# Headlight_Left_Board.net
KiCad netlist of a schematic drawn in Altium Designer
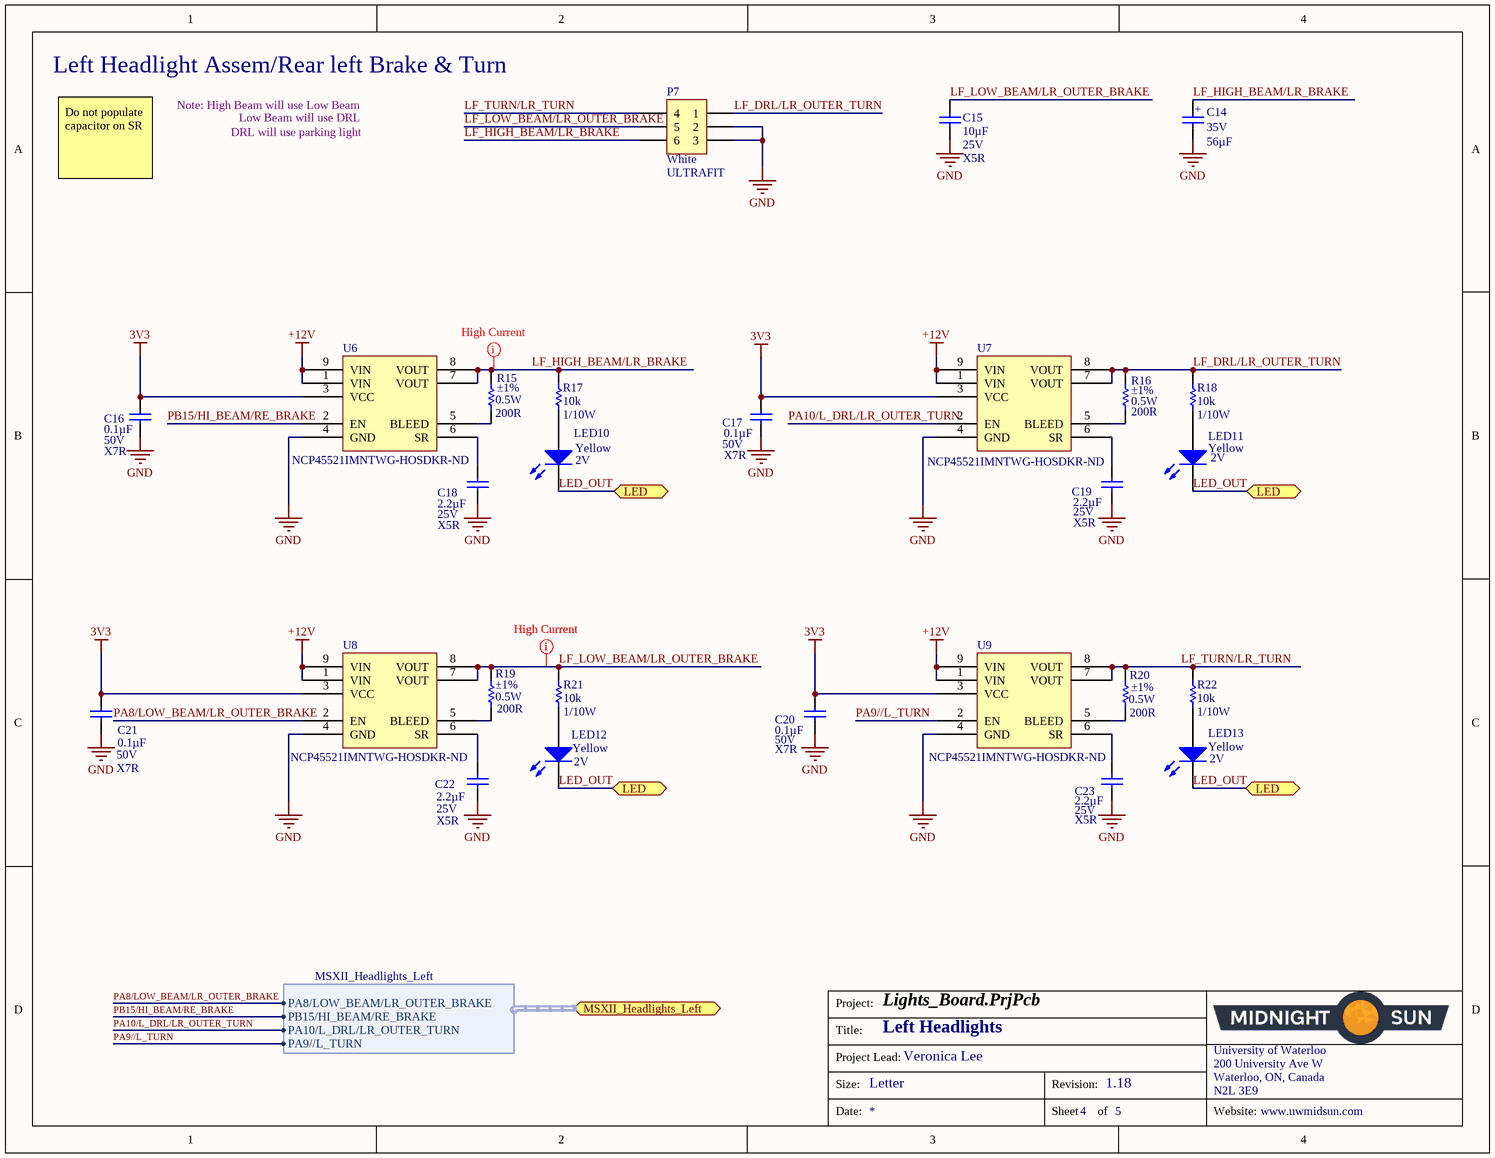
[diagram p0: Headlight_Left_Board.SchDoc]

(export (version "E")
  (design (tool "Eeschema 10.0.6"))
  (components
    (comp (ref "C14")
      (value "CAP ALUM 56UF 20% 35V RADIAL")
      (footprint "CAP ALUM 56UF 20% 35V RADIAL")
      (description "56µF 35V Aluminum Electrolytic Capacitors Radial, Can 1000 Hrs @ 105°C")
      (fields
        (field (name "MANUFACTURER") "Panasonic Electronic Components")
        (field (name "MANUFACTURER PART NUMBER") "EEU-FC1V560H")
        (field (name "VOLTAGE") "35V")
        (field (name "CAPACITANCE") "56µF")
      )
      (libsource (lib "Schematic Diagrams") (part "CAP ALUM 56UF 20% 35V RADIAL"))
    )
    (comp (ref "C15")
      (value "CAP CER 10uF 25V 20% X5R 0603")
      (footprint "CAP, 0603")
      (description "10µF ±20% 25V Ceramic Capacitor X5R 0603 (1608 Metric)")
      (fields
        (field (name "TOLERANCE") "±20%")
        (field (name "CAPACITANCE") "10µF")
        (field (name "VOLTAGE") "25V")
        (field (name "TEMPERATURE COEFFICIENT") "X5R")
      )
      (libsource (lib "Schematic Diagrams") (part "CAP CER 10uF 25V 20% X5R 0603"))
    )
    (comp (ref "C16")
      (value "CAP CER 0.1UF 50V 10% X7R 0603")
      (footprint "CAP, 0603")
      (description "0.10µF ±10% 50V Ceramic Capacitor X7R 0603 (1608 Metric)")
      (fields
        (field (name "TOLERANCE") "±10%")
        (field (name "CAPACITANCE") "0.1µF")
        (field (name "VOLTAGE") "50V")
        (field (name "TEMPERATURE COEFFICIENT") "X7R")
      )
      (libsource (lib "Schematic Diagrams") (part "CAP CER 0.1UF 50V 10% X7R 0603"))
    )
    (comp (ref "C17")
      (value "CAP CER 0.1UF 50V 10% X7R 0603")
      (footprint "CAP, 0603")
      (description "0.10µF ±10% 50V Ceramic Capacitor X7R 0603 (1608 Metric)")
      (fields
        (field (name "TOLERANCE") "±10%")
        (field (name "CAPACITANCE") "0.1µF")
        (field (name "VOLTAGE") "50V")
        (field (name "TEMPERATURE COEFFICIENT") "X7R")
      )
      (libsource (lib "Schematic Diagrams") (part "CAP CER 0.1UF 50V 10% X7R 0603"))
    )
    (comp (ref "C18")
      (value "CAP CER 2.2UF 25V 10% X5R 0603")
      (footprint "CAP, 0603")
      (description "2.2µF ±10% 25V Ceramic Capacitor X5R 0603 (1608 Metric)")
      (fields
        (field (name "TOLERANCE") "±10%")
        (field (name "CAPACITANCE") "2.2µF")
        (field (name "VOLTAGE") "25V")
        (field (name "TEMPERATURE COEFFICIENT") "X5R")
      )
      (libsource (lib "Schematic Diagrams") (part "CAP CER 2.2UF 25V 10% X5R 0603"))
    )
    (comp (ref "C19")
      (value "CAP CER 2.2UF 25V 10% X5R 0603")
      (footprint "CAP, 0603")
      (description "2.2µF ±10% 25V Ceramic Capacitor X5R 0603 (1608 Metric)")
      (fields
        (field (name "TOLERANCE") "±10%")
        (field (name "CAPACITANCE") "2.2µF")
        (field (name "VOLTAGE") "25V")
        (field (name "TEMPERATURE COEFFICIENT") "X5R")
      )
      (libsource (lib "Schematic Diagrams") (part "CAP CER 2.2UF 25V 10% X5R 0603"))
    )
    (comp (ref "C20")
      (value "CAP CER 0.1UF 50V 10% X7R 0603")
      (footprint "CAP, 0603")
      (description "0.10µF ±10% 50V Ceramic Capacitor X7R 0603 (1608 Metric)")
      (fields
        (field (name "TOLERANCE") "±10%")
        (field (name "CAPACITANCE") "0.1µF")
        (field (name "VOLTAGE") "50V")
        (field (name "TEMPERATURE COEFFICIENT") "X7R")
      )
      (libsource (lib "Schematic Diagrams") (part "CAP CER 0.1UF 50V 10% X7R 0603"))
    )
    (comp (ref "C21")
      (value "CAP CER 0.1UF 50V 10% X7R 0603")
      (footprint "CAP, 0603")
      (description "0.10µF ±10% 50V Ceramic Capacitor X7R 0603 (1608 Metric)")
      (fields
        (field (name "TOLERANCE") "±10%")
        (field (name "CAPACITANCE") "0.1µF")
        (field (name "VOLTAGE") "50V")
        (field (name "TEMPERATURE COEFFICIENT") "X7R")
      )
      (libsource (lib "Schematic Diagrams") (part "CAP CER 0.1UF 50V 10% X7R 0603"))
    )
    (comp (ref "C22")
      (value "CAP CER 2.2UF 25V 10% X5R 0603")
      (footprint "CAP, 0603")
      (description "2.2µF ±10% 25V Ceramic Capacitor X5R 0603 (1608 Metric)")
      (fields
        (field (name "TOLERANCE") "±10%")
        (field (name "CAPACITANCE") "2.2µF")
        (field (name "VOLTAGE") "25V")
        (field (name "TEMPERATURE COEFFICIENT") "X5R")
      )
      (libsource (lib "Schematic Diagrams") (part "CAP CER 2.2UF 25V 10% X5R 0603"))
    )
    (comp (ref "C23")
      (value "CAP CER 2.2UF 25V 10% X5R 0603")
      (footprint "CAP, 0603")
      (description "2.2µF ±10% 25V Ceramic Capacitor X5R 0603 (1608 Metric)")
      (fields
        (field (name "TOLERANCE") "±10%")
        (field (name "CAPACITANCE") "2.2µF")
        (field (name "VOLTAGE") "25V")
        (field (name "TEMPERATURE COEFFICIENT") "X5R")
      )
      (libsource (lib "Schematic Diagrams") (part "CAP CER 2.2UF 25V 10% X5R 0603"))
    )
    (comp (ref "LED10")
      (value "LED YELLOW CLEAR 2.1V 0603")
      (footprint "LED_0603")
      (description "Yellow 590nm LED Indication - Discrete 2V 0603 (1608 Metric)")
      (fields
        (field (name "MANUFACTURER") "Wurth Electronics Inc.")
        (field (name "MANUFACTURER PART NUMBER") "150060YS75000")
        (field (name "COLOR") "Yellow")
        (field (name "VOLTAGE - FORWARD (VF) (TYP)") "2V")
      )
      (libsource (lib "Schematic Diagrams") (part "LED YELLOW CLEAR 2.1V 0603"))
    )
    (comp (ref "LED11")
      (value "LED YELLOW CLEAR 2.1V 0603")
      (footprint "LED_0603")
      (description "Yellow 590nm LED Indication - Discrete 2V 0603 (1608 Metric)")
      (fields
        (field (name "MANUFACTURER") "Wurth Electronics Inc.")
        (field (name "MANUFACTURER PART NUMBER") "150060YS75000")
        (field (name "COLOR") "Yellow")
        (field (name "VOLTAGE - FORWARD (VF) (TYP)") "2V")
      )
      (libsource (lib "Schematic Diagrams") (part "LED YELLOW CLEAR 2.1V 0603"))
    )
    (comp (ref "LED12")
      (value "LED YELLOW CLEAR 2.1V 0603")
      (footprint "LED_0603")
      (description "Yellow 590nm LED Indication - Discrete 2V 0603 (1608 Metric)")
      (fields
        (field (name "MANUFACTURER") "Wurth Electronics Inc.")
        (field (name "MANUFACTURER PART NUMBER") "150060YS75000")
        (field (name "COLOR") "Yellow")
        (field (name "VOLTAGE - FORWARD (VF) (TYP)") "2V")
      )
      (libsource (lib "Schematic Diagrams") (part "LED YELLOW CLEAR 2.1V 0603"))
    )
    (comp (ref "LED13")
      (value "LED YELLOW CLEAR 2.1V 0603")
      (footprint "LED_0603")
      (description "Yellow 590nm LED Indication - Discrete 2V 0603 (1608 Metric)")
      (fields
        (field (name "MANUFACTURER") "Wurth Electronics Inc.")
        (field (name "MANUFACTURER PART NUMBER") "150060YS75000")
        (field (name "COLOR") "Yellow")
        (field (name "VOLTAGE - FORWARD (VF) (TYP)") "2V")
      )
      (libsource (lib "Schematic Diagrams") (part "LED YELLOW CLEAR 2.1V 0603"))
    )
    (comp (ref "P7")
      (value "CONN 6POS ULTRA-FIT NATURAL COLOR 0.138\"")
      (footprint "CONN, 6POS ULTRA-FIT - NATURAL COLOR")
      (description "6 Positions Header Connector 0.138\" (3.50mm) Through Hole Tin")
      (fields (field (name "INSULATION COLOR") "White") (field (name "SERIES") "ULTRAFIT"))
      (libsource (lib "Schematic Diagrams") (part "CONN 6POS ULTRA-FIT NATURAL COLOR 0.138{dblquote}"))
    )
    (comp (ref "R15")
      (value "200R")
      (footprint "RES 0805")
      (fields
        (field (name "MANUFACTURER") "Panasonic Electronic Components")
        (field (name "MANUFACTURER PART NUMBER") "ERJ-P06F2000V")
        (field (name "TOLERANCE") "±1%")
        (field (name "POWER (WATTS)") "0.5W")
        (field (name "Comment") "RES SMD 200 OHM 1% 1/2W 0805")
      )
      (libsource (lib "Schematic Diagrams") (part "RES SMD 200 OHM 1% 1/2W 0805"))
    )
    (comp (ref "R16")
      (value "200R")
      (footprint "RES 0805")
      (fields
        (field (name "MANUFACTURER") "Panasonic Electronic Components")
        (field (name "MANUFACTURER PART NUMBER") "ERJ-P06F2000V")
        (field (name "TOLERANCE") "±1%")
        (field (name "POWER (WATTS)") "0.5W")
        (field (name "Comment") "RES SMD 200 OHM 1% 1/2W 0805")
      )
      (libsource (lib "Schematic Diagrams") (part "RES SMD 200 OHM 1% 1/2W 0805"))
    )
    (comp (ref "R17")
      (value "RES 10K OHM 1% 1/10W 0603")
      (footprint "RES, 0603")
      (description "RES SMD 10K OHM 1% 1/10W 0603")
      (fields
        (field (name "TOLERANCE") "±1%")
        (field (name "RESISTANCE") "10k")
        (field (name "POWER") "1/10W")
      )
      (libsource (lib "Schematic Diagrams") (part "RES 10K OHM 1% 1/10W 0603"))
    )
    (comp (ref "R18")
      (value "RES 10K OHM 1% 1/10W 0603")
      (footprint "RES, 0603")
      (description "RES SMD 10K OHM 1% 1/10W 0603")
      (fields
        (field (name "TOLERANCE") "±1%")
        (field (name "RESISTANCE") "10k")
        (field (name "POWER") "1/10W")
      )
      (libsource (lib "Schematic Diagrams") (part "RES 10K OHM 1% 1/10W 0603"))
    )
    (comp (ref "R19")
      (value "200R")
      (footprint "RES 0805")
      (fields
        (field (name "MANUFACTURER") "Panasonic Electronic Components")
        (field (name "MANUFACTURER PART NUMBER") "ERJ-P06F2000V")
        (field (name "TOLERANCE") "±1%")
        (field (name "POWER (WATTS)") "0.5W")
        (field (name "Comment") "RES SMD 200 OHM 1% 1/2W 0805")
      )
      (libsource (lib "Schematic Diagrams") (part "RES SMD 200 OHM 1% 1/2W 0805"))
    )
    (comp (ref "R20")
      (value "200R")
      (footprint "RES 0805")
      (fields
        (field (name "MANUFACTURER") "Panasonic Electronic Components")
        (field (name "MANUFACTURER PART NUMBER") "ERJ-P06F2000V")
        (field (name "TOLERANCE") "±1%")
        (field (name "POWER (WATTS)") "0.5W")
        (field (name "Comment") "RES SMD 200 OHM 1% 1/2W 0805")
      )
      (libsource (lib "Schematic Diagrams") (part "RES SMD 200 OHM 1% 1/2W 0805"))
    )
    (comp (ref "R21")
      (value "RES 10K OHM 1% 1/10W 0603")
      (footprint "RES, 0603")
      (description "RES SMD 10K OHM 1% 1/10W 0603")
      (fields
        (field (name "TOLERANCE") "±1%")
        (field (name "RESISTANCE") "10k")
        (field (name "POWER") "1/10W")
      )
      (libsource (lib "Schematic Diagrams") (part "RES 10K OHM 1% 1/10W 0603"))
    )
    (comp (ref "R22")
      (value "RES 10K OHM 1% 1/10W 0603")
      (footprint "RES, 0603")
      (description "RES SMD 10K OHM 1% 1/10W 0603")
      (fields
        (field (name "TOLERANCE") "±1%")
        (field (name "RESISTANCE") "10k")
        (field (name "POWER") "1/10W")
      )
      (libsource (lib "Schematic Diagrams") (part "RES 10K OHM 1% 1/10W 0603"))
    )
    (comp (ref "U6")
      (value "IC LOAD SWITCH ACT-HI 10.5A 8DFN")
      (footprint "IC LOAD SWITCH ACT-HI 10.5A 8DFN")
      (description "NCP45521IMNTWG-H")
      (fields
        (field (name "MANUFACTURER") "ON Semiconductor")
        (field (name "SUPPLIER PART NUMBER 2") "NCP45521IMNTWG-HOSDKR-ND")
      )
      (libsource (lib "Schematic Diagrams") (part "IC LOAD SWITCH ACT-HI 10.5A 8DFN"))
    )
    (comp (ref "U7")
      (value "IC LOAD SWITCH ACT-HI 10.5A 8DFN")
      (footprint "IC LOAD SWITCH ACT-HI 10.5A 8DFN")
      (description "NCP45521IMNTWG-H")
      (fields
        (field (name "MANUFACTURER") "ON Semiconductor")
        (field (name "SUPPLIER PART NUMBER 2") "NCP45521IMNTWG-HOSDKR-ND")
      )
      (libsource (lib "Schematic Diagrams") (part "IC LOAD SWITCH ACT-HI 10.5A 8DFN"))
    )
    (comp (ref "U8")
      (value "IC LOAD SWITCH ACT-HI 10.5A 8DFN")
      (footprint "IC LOAD SWITCH ACT-HI 10.5A 8DFN")
      (description "NCP45521IMNTWG-H")
      (fields
        (field (name "MANUFACTURER") "ON Semiconductor")
        (field (name "SUPPLIER PART NUMBER 2") "NCP45521IMNTWG-HOSDKR-ND")
      )
      (libsource (lib "Schematic Diagrams") (part "IC LOAD SWITCH ACT-HI 10.5A 8DFN"))
    )
    (comp (ref "U9")
      (value "IC LOAD SWITCH ACT-HI 10.5A 8DFN")
      (footprint "IC LOAD SWITCH ACT-HI 10.5A 8DFN")
      (description "NCP45521IMNTWG-H")
      (fields
        (field (name "MANUFACTURER") "ON Semiconductor")
        (field (name "SUPPLIER PART NUMBER 2") "NCP45521IMNTWG-HOSDKR-ND")
      )
      (libsource (lib "Schematic Diagrams") (part "IC LOAD SWITCH ACT-HI 10.5A 8DFN"))
    )
  )
  (nets
    (net (code "2") (name "+12V") (class "Default")
      (node (ref "U6") (pin "1") (pinfunction "VIN_1") (pintype "passive"))
      (node (ref "U6") (pin "9") (pinfunction "VIN_9") (pintype "passive"))
      (node (ref "U7") (pin "1") (pinfunction "VIN_1") (pintype "passive"))
      (node (ref "U7") (pin "9") (pinfunction "VIN_9") (pintype "passive"))
      (node (ref "U8") (pin "1") (pinfunction "VIN_1") (pintype "passive"))
      (node (ref "U8") (pin "9") (pinfunction "VIN_9") (pintype "passive"))
      (node (ref "U9") (pin "1") (pinfunction "VIN_1") (pintype "passive"))
      (node (ref "U9") (pin "9") (pinfunction "VIN_9") (pintype "passive"))
    )
    (net (code "3") (name "/LED_OUT") (class "Default")
      (node (ref "LED10") (pin "2") (pinfunction "K_2") (pintype "passive"))
      (node (ref "LED11") (pin "2") (pinfunction "K_2") (pintype "passive"))
      (node (ref "LED12") (pin "2") (pinfunction "K_2") (pintype "passive"))
      (node (ref "LED13") (pin "2") (pinfunction "K_2") (pintype "passive"))
    )
    (net (code "4") (name "/LF_DRL{slash}LR_OUTER_TURN") (class "Default")
      (node (ref "P7") (pin "1") (pinfunction "1_1") (pintype "passive"))
      (node (ref "R16") (pin "1") (pinfunction "1_1") (pintype "passive"))
      (node (ref "R18") (pin "1") (pinfunction "1_1") (pintype "passive"))
      (node (ref "U7") (pin "7") (pinfunction "VOUT_7") (pintype "passive"))
      (node (ref "U7") (pin "8") (pinfunction "VOUT_8") (pintype "passive"))
    )
    (net (code "5") (name "/LF_HIGH_BEAM{slash}LR_BRAKE") (class "Default")
      (node (ref "C14") (pin "1") (pinfunction "1_1") (pintype "passive"))
      (node (ref "P7") (pin "6") (pinfunction "6_6") (pintype "passive"))
      (node (ref "R15") (pin "1") (pinfunction "1_1") (pintype "passive"))
      (node (ref "R17") (pin "1") (pinfunction "1_1") (pintype "passive"))
      (node (ref "U6") (pin "7") (pinfunction "VOUT_7") (pintype "passive"))
      (node (ref "U6") (pin "8") (pinfunction "VOUT_8") (pintype "passive"))
    )
    (net (code "6") (name "/LF_LOW_BEAM{slash}LR_OUTER_BRAKE") (class "Default")
      (node (ref "C15") (pin "2") (pinfunction "2_2") (pintype "passive"))
      (node (ref "P7") (pin "5") (pinfunction "5_5") (pintype "passive"))
      (node (ref "R19") (pin "1") (pinfunction "1_1") (pintype "passive"))
      (node (ref "R21") (pin "1") (pinfunction "1_1") (pintype "passive"))
      (node (ref "U8") (pin "7") (pinfunction "VOUT_7") (pintype "passive"))
      (node (ref "U8") (pin "8") (pinfunction "VOUT_8") (pintype "passive"))
    )
    (net (code "7") (name "/LF_TURN{slash}LR_TURN") (class "Default")
      (node (ref "P7") (pin "4") (pinfunction "4_4") (pintype "passive"))
      (node (ref "R20") (pin "1") (pinfunction "1_1") (pintype "passive"))
      (node (ref "R22") (pin "1") (pinfunction "1_1") (pintype "passive"))
      (node (ref "U9") (pin "7") (pinfunction "VOUT_7") (pintype "passive"))
      (node (ref "U9") (pin "8") (pinfunction "VOUT_8") (pintype "passive"))
    )
    (net (code "8") (name "/PA8{slash}LOW_BEAM{slash}LR_OUTER_BRAKE") (class "Default")
      (node (ref "U8") (pin "2") (pinfunction "EN_2") (pintype "passive"))
    )
    (net (code "9") (name "/PA9{slash}{slash}L_TURN") (class "Default")
      (node (ref "U9") (pin "2") (pinfunction "EN_2") (pintype "passive"))
    )
    (net (code "10") (name "/PA10{slash}L_DRL{slash}LR_OUTER_TURN") (class "Default")
      (node (ref "U7") (pin "2") (pinfunction "EN_2") (pintype "passive"))
    )
    (net (code "11") (name "/PB15{slash}HI_BEAM{slash}RE_BRAKE") (class "Default")
      (node (ref "U6") (pin "2") (pinfunction "EN_2") (pintype "passive"))
    )
    (net (code "13") (name "3V3") (class "Default")
      (node (ref "C16") (pin "1") (pinfunction "1_1") (pintype "passive"))
      (node (ref "C17") (pin "1") (pinfunction "1_1") (pintype "passive"))
      (node (ref "C20") (pin "1") (pinfunction "1_1") (pintype "passive"))
      (node (ref "C21") (pin "1") (pinfunction "1_1") (pintype "passive"))
      (node (ref "U6") (pin "3") (pinfunction "VCC_3") (pintype "passive"))
      (node (ref "U7") (pin "3") (pinfunction "VCC_3") (pintype "passive"))
      (node (ref "U8") (pin "3") (pinfunction "VCC_3") (pintype "passive"))
      (node (ref "U9") (pin "3") (pinfunction "VCC_3") (pintype "passive"))
    )
    (net (code "14") (name "GND") (class "Default")
      (node (ref "C14") (pin "2") (pinfunction "2_2") (pintype "passive"))
      (node (ref "C15") (pin "1") (pinfunction "1_1") (pintype "passive"))
      (node (ref "C16") (pin "2") (pinfunction "2_2") (pintype "passive"))
      (node (ref "C17") (pin "2") (pinfunction "2_2") (pintype "passive"))
      (node (ref "C18") (pin "2") (pinfunction "2_2") (pintype "passive"))
      (node (ref "C19") (pin "2") (pinfunction "2_2") (pintype "passive"))
      (node (ref "C20") (pin "2") (pinfunction "2_2") (pintype "passive"))
      (node (ref "C21") (pin "2") (pinfunction "2_2") (pintype "passive"))
      (node (ref "C22") (pin "2") (pinfunction "2_2") (pintype "passive"))
      (node (ref "C23") (pin "2") (pinfunction "2_2") (pintype "passive"))
      (node (ref "P7") (pin "2") (pinfunction "2_2") (pintype "passive"))
      (node (ref "P7") (pin "3") (pinfunction "3_3") (pintype "passive"))
      (node (ref "U6") (pin "4") (pinfunction "GND_4") (pintype "passive"))
      (node (ref "U7") (pin "4") (pinfunction "GND_4") (pintype "passive"))
      (node (ref "U8") (pin "4") (pinfunction "GND_4") (pintype "passive"))
      (node (ref "U9") (pin "4") (pinfunction "GND_4") (pintype "passive"))
    )
    (net (code "15") (name "Net-(LED10-A)") (class "Default")
      (node (ref "LED10") (pin "1") (pinfunction "A_1") (pintype "passive"))
      (node (ref "R17") (pin "2") (pinfunction "2_2") (pintype "passive"))
    )
    (net (code "16") (name "Net-(LED11-A)") (class "Default")
      (node (ref "LED11") (pin "1") (pinfunction "A_1") (pintype "passive"))
      (node (ref "R18") (pin "2") (pinfunction "2_2") (pintype "passive"))
    )
    (net (code "17") (name "Net-(LED12-A)") (class "Default")
      (node (ref "LED12") (pin "1") (pinfunction "A_1") (pintype "passive"))
      (node (ref "R21") (pin "2") (pinfunction "2_2") (pintype "passive"))
    )
    (net (code "18") (name "Net-(LED13-A)") (class "Default")
      (node (ref "LED13") (pin "1") (pinfunction "A_1") (pintype "passive"))
      (node (ref "R22") (pin "2") (pinfunction "2_2") (pintype "passive"))
    )
    (net (code "19") (name "Net-(U6-BLEED)") (class "Default")
      (node (ref "R15") (pin "2") (pinfunction "2_2") (pintype "passive"))
      (node (ref "U6") (pin "5") (pinfunction "BLEED_5") (pintype "passive"))
    )
    (net (code "20") (name "Net-(U6-SR)") (class "Default")
      (node (ref "C18") (pin "1") (pinfunction "1_1") (pintype "passive"))
      (node (ref "U6") (pin "6") (pinfunction "SR_6") (pintype "passive"))
    )
    (net (code "21") (name "Net-(U7-BLEED)") (class "Default")
      (node (ref "R16") (pin "2") (pinfunction "2_2") (pintype "passive"))
      (node (ref "U7") (pin "5") (pinfunction "BLEED_5") (pintype "passive"))
    )
    (net (code "22") (name "Net-(U7-SR)") (class "Default")
      (node (ref "C19") (pin "1") (pinfunction "1_1") (pintype "passive"))
      (node (ref "U7") (pin "6") (pinfunction "SR_6") (pintype "passive"))
    )
    (net (code "23") (name "Net-(U8-BLEED)") (class "Default")
      (node (ref "R19") (pin "2") (pinfunction "2_2") (pintype "passive"))
      (node (ref "U8") (pin "5") (pinfunction "BLEED_5") (pintype "passive"))
    )
    (net (code "24") (name "Net-(U8-SR)") (class "Default")
      (node (ref "C22") (pin "1") (pinfunction "1_1") (pintype "passive"))
      (node (ref "U8") (pin "6") (pinfunction "SR_6") (pintype "passive"))
    )
    (net (code "25") (name "Net-(U9-BLEED)") (class "Default")
      (node (ref "R20") (pin "2") (pinfunction "2_2") (pintype "passive"))
      (node (ref "U9") (pin "5") (pinfunction "BLEED_5") (pintype "passive"))
    )
    (net (code "26") (name "Net-(U9-SR)") (class "Default")
      (node (ref "C23") (pin "1") (pinfunction "1_1") (pintype "passive"))
      (node (ref "U9") (pin "6") (pinfunction "SR_6") (pintype "passive"))
    )
  )
)
